# axiom_beta_interface_dummy_v0_12.net
KiCad netlist of a schematic drawn in EAGLE
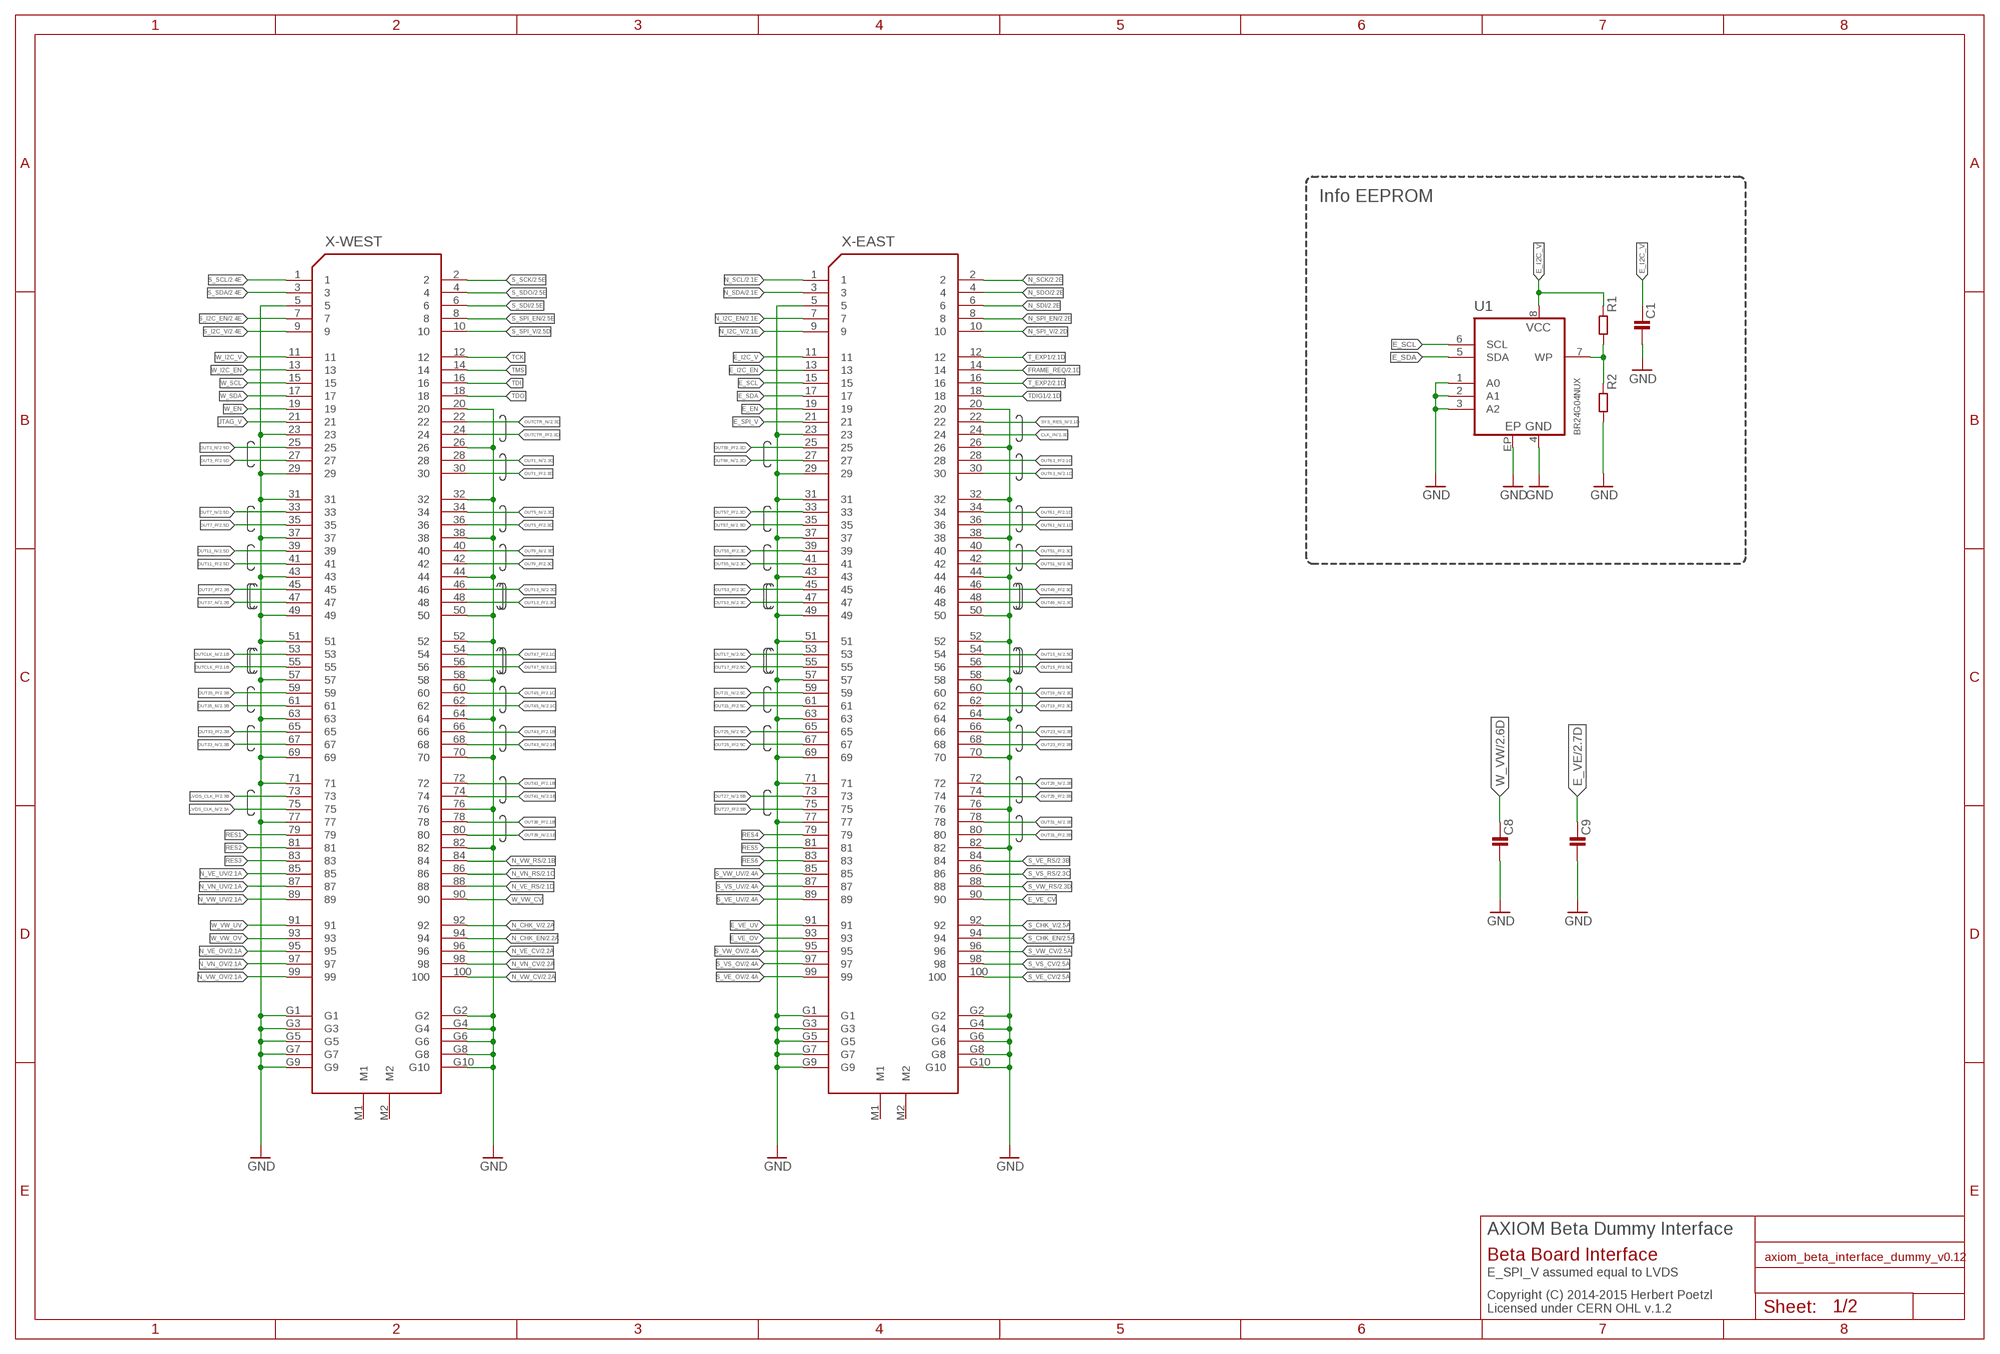
[diagram p0: schematic, sheet 1]
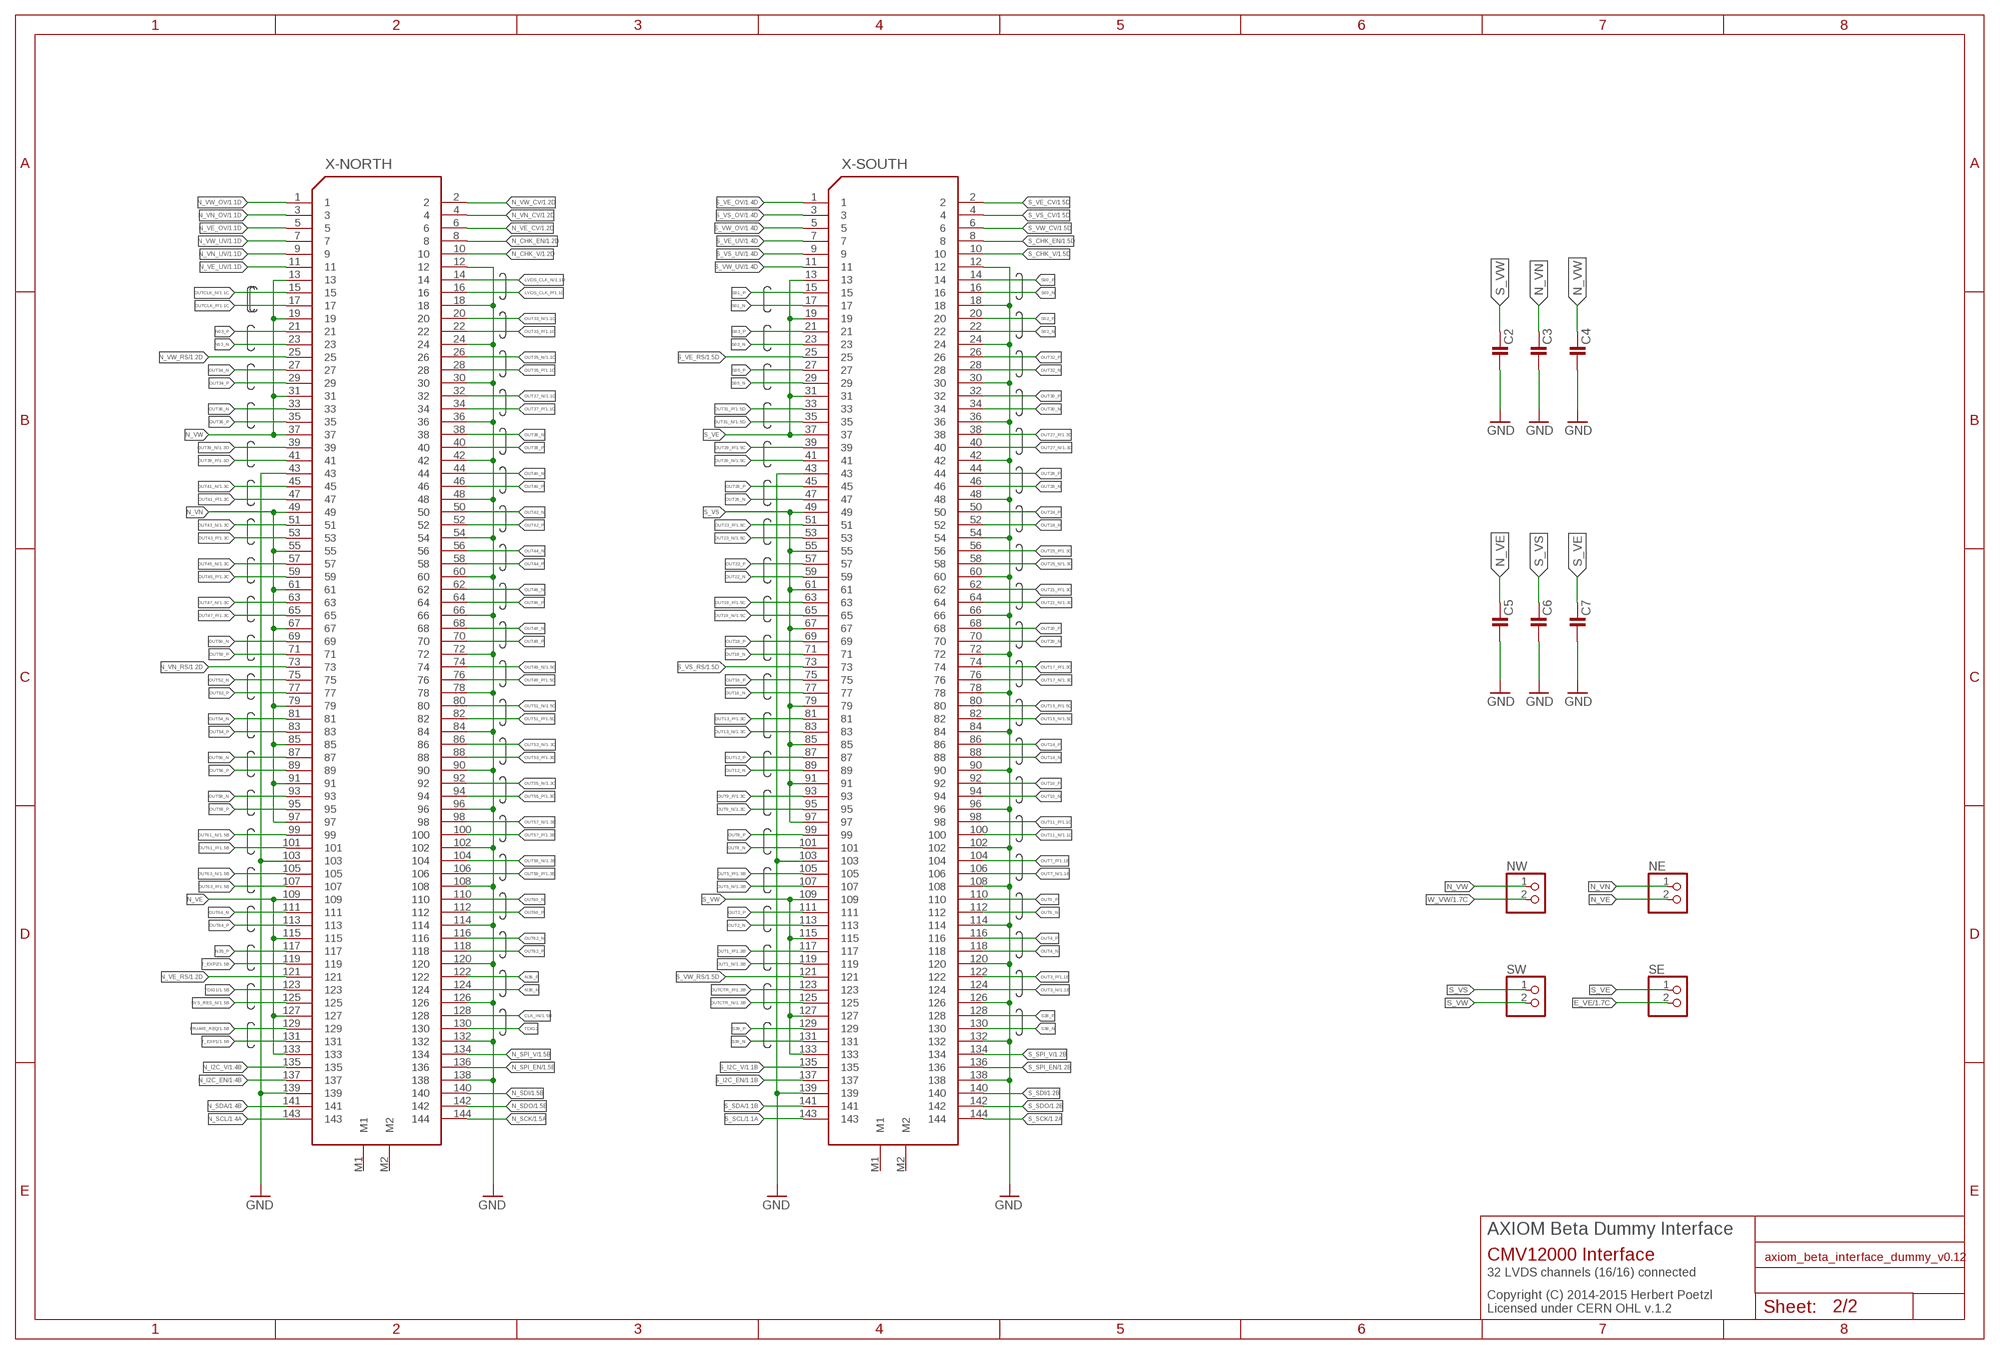
[diagram p1: schematic, sheet 2]

(export (version "E")
  (design (tool "Eeschema 10.0.6"))
  (components
    (comp (ref "C2")
      (value "C0805-B")
      (footprint "eagle-import:0805-B")
      (libsource (lib "eagle-import") (part "C0805-B"))
    )
    (comp (ref "C3")
      (value "C0805-B")
      (footprint "eagle-import:0805-B")
      (libsource (lib "eagle-import") (part "C0805-B"))
    )
    (comp (ref "C4")
      (value "C0805-B")
      (footprint "eagle-import:0805-B")
      (libsource (lib "eagle-import") (part "C0805-B"))
    )
    (comp (ref "C5")
      (value "C0805-B")
      (footprint "eagle-import:0805-B")
      (libsource (lib "eagle-import") (part "C0805-B"))
    )
    (comp (ref "C6")
      (value "C0805-B")
      (footprint "eagle-import:0805-B")
      (libsource (lib "eagle-import") (part "C0805-B"))
    )
    (comp (ref "C7")
      (value "C0805-B")
      (footprint "eagle-import:0805-B")
      (libsource (lib "eagle-import") (part "C0805-B"))
    )
    (comp (ref "NE")
      (value "PINHD-1X02_2.54")
      (footprint "eagle-import:1X02")
      (libsource (lib "eagle-import") (part "PINHD-1X02_2.54"))
    )
    (comp (ref "NW")
      (value "PINHD-1X02_2.54")
      (footprint "eagle-import:1X02")
      (libsource (lib "eagle-import") (part "PINHD-1X02_2.54"))
    )
    (comp (ref "SE")
      (value "PINHD-1X02_2.54")
      (footprint "eagle-import:1X02")
      (libsource (lib "eagle-import") (part "PINHD-1X02_2.54"))
    )
    (comp (ref "SW")
      (value "PINHD-1X02_2.54")
      (footprint "eagle-import:1X02")
      (libsource (lib "eagle-import") (part "PINHD-1X02_2.54"))
    )
    (comp (ref "X-NORTH")
      (value "FX10-144S")
      (footprint "eagle-import:FX10A-144S")
      (libsource (lib "eagle-import") (part "FX10-144S"))
    )
    (comp (ref "X-SOUTH")
      (value "FX10-144S")
      (footprint "eagle-import:FX10A-144S")
      (libsource (lib "eagle-import") (part "FX10-144S"))
    )
    (comp (ref "C1")
      (value "C0402-B")
      (footprint "eagle-import:0402-B")
      (libsource (lib "eagle-import") (part "C0402-B"))
    )
    (comp (ref "C8")
      (value "C0805-B")
      (footprint "eagle-import:0805-B")
      (libsource (lib "eagle-import") (part "C0805-B"))
    )
    (comp (ref "C9")
      (value "C0805-B")
      (footprint "eagle-import:0805-B")
      (libsource (lib "eagle-import") (part "C0805-B"))
    )
    (comp (ref "R1")
      (value "R0402-B")
      (footprint "eagle-import:0402-B")
      (libsource (lib "eagle-import") (part "R0402-B"))
    )
    (comp (ref "R2")
      (value "R0402-B")
      (footprint "eagle-import:0402-B")
      (libsource (lib "eagle-import") (part "R0402-B"))
    )
    (comp (ref "U1")
      (value "BR24G04NUX")
      (footprint "eagle-import:DFN200X300X100-9N")
      (libsource (lib "eagle-import") (part "BR24G04NUX"))
    )
    (comp (ref "X-EAST")
      (value "FX10-100/10P")
      (footprint "eagle-import:FX10A-100P_10")
      (libsource (lib "eagle-import") (part "FX10-100/10P"))
    )
    (comp (ref "X-WEST")
      (value "FX10-100/10P")
      (footprint "eagle-import:FX10A-100P_10")
      (libsource (lib "eagle-import") (part "FX10-100/10P"))
    )
  )
  (nets
    (net (code "1") (name "CLK_IN") (class "Default")
      (node (ref "X-EAST") (pin "24") (pinfunction "24_24") (pintype "bidirectional"))
      (node (ref "X-NORTH") (pin "128") (pinfunction "128_128") (pintype "bidirectional"))
    )
    (net (code "2") (name "E_EN") (class "Default")
      (node (ref "X-EAST") (pin "19") (pinfunction "19_19") (pintype "bidirectional"))
    )
    (net (code "3") (name "E_I2C_EN") (class "Default")
      (node (ref "X-EAST") (pin "13") (pinfunction "13_13") (pintype "bidirectional"))
    )
    (net (code "4") (name "E_I2C_V") (class "Default")
      (node (ref "C1") (pin "1") (pinfunction "1_1") (pintype "passive"))
      (node (ref "R1") (pin "1") (pinfunction "1_1") (pintype "passive"))
      (node (ref "U1") (pin "8") (pinfunction "VCC_8") (pintype "power_in"))
      (node (ref "X-EAST") (pin "11") (pinfunction "11_11") (pintype "bidirectional"))
    )
    (net (code "5") (name "E_SCL") (class "Default")
      (node (ref "U1") (pin "6") (pinfunction "SCL_6") (pintype "input"))
      (node (ref "X-EAST") (pin "15") (pinfunction "15_15") (pintype "bidirectional"))
    )
    (net (code "6") (name "E_SDA") (class "Default")
      (node (ref "U1") (pin "5") (pinfunction "SDA_5") (pintype "bidirectional"))
      (node (ref "X-EAST") (pin "17") (pinfunction "17_17") (pintype "bidirectional"))
    )
    (net (code "7") (name "E_SPI_V") (class "Default")
      (node (ref "X-EAST") (pin "21") (pinfunction "21_21") (pintype "bidirectional"))
    )
    (net (code "8") (name "E_VE") (class "Default")
      (node (ref "C9") (pin "1") (pinfunction "1_1") (pintype "passive"))
      (node (ref "SE") (pin "2") (pinfunction "2_2") (pintype "passive"))
    )
    (net (code "9") (name "E_VE_CV") (class "Default")
      (node (ref "X-EAST") (pin "90") (pinfunction "90_90") (pintype "bidirectional"))
    )
    (net (code "10") (name "E_VE_OV") (class "Default")
      (node (ref "X-EAST") (pin "93") (pinfunction "93_93") (pintype "bidirectional"))
    )
    (net (code "11") (name "E_VE_UV") (class "Default")
      (node (ref "X-EAST") (pin "91") (pinfunction "91_91") (pintype "bidirectional"))
    )
    (net (code "12") (name "FRAME_REQ") (class "Default")
      (node (ref "X-EAST") (pin "14") (pinfunction "14_14") (pintype "bidirectional"))
      (node (ref "X-NORTH") (pin "129") (pinfunction "129_129") (pintype "bidirectional"))
    )
    (net (code "13") (name "GND") (class "Default")
      (node (ref "C1") (pin "2") (pinfunction "2_2") (pintype "passive"))
      (node (ref "C2") (pin "2") (pinfunction "2_2") (pintype "passive"))
      (node (ref "C3") (pin "2") (pinfunction "2_2") (pintype "passive"))
      (node (ref "C4") (pin "2") (pinfunction "2_2") (pintype "passive"))
      (node (ref "C5") (pin "2") (pinfunction "2_2") (pintype "passive"))
      (node (ref "C6") (pin "2") (pinfunction "2_2") (pintype "passive"))
      (node (ref "C7") (pin "2") (pinfunction "2_2") (pintype "passive"))
      (node (ref "C8") (pin "2") (pinfunction "2_2") (pintype "passive"))
      (node (ref "C9") (pin "2") (pinfunction "2_2") (pintype "passive"))
      (node (ref "R2") (pin "2") (pinfunction "2_2") (pintype "passive"))
      (node (ref "U1") (pin "1") (pinfunction "A0_1") (pintype "input"))
      (node (ref "U1") (pin "2") (pinfunction "A1_2") (pintype "input"))
      (node (ref "U1") (pin "3") (pinfunction "A2_3") (pintype "input"))
      (node (ref "U1") (pin "4") (pinfunction "GND_4") (pintype "passive"))
      (node (ref "U1") (pin "EP") (pinfunction "EP_EP") (pintype "passive"))
      (node (ref "X-EAST") (pin "20") (pinfunction "20_20") (pintype "bidirectional"))
      (node (ref "X-EAST") (pin "23") (pinfunction "23_23") (pintype "bidirectional"))
      (node (ref "X-EAST") (pin "26") (pinfunction "26_26") (pintype "bidirectional"))
      (node (ref "X-EAST") (pin "29") (pinfunction "29_29") (pintype "bidirectional"))
      (node (ref "X-EAST") (pin "31") (pinfunction "31_31") (pintype "bidirectional"))
      (node (ref "X-EAST") (pin "32") (pinfunction "32_32") (pintype "bidirectional"))
      (node (ref "X-EAST") (pin "37") (pinfunction "37_37") (pintype "bidirectional"))
      (node (ref "X-EAST") (pin "38") (pinfunction "38_38") (pintype "bidirectional"))
      (node (ref "X-EAST") (pin "43") (pinfunction "43_43") (pintype "bidirectional"))
      (node (ref "X-EAST") (pin "44") (pinfunction "44_44") (pintype "bidirectional"))
      (node (ref "X-EAST") (pin "49") (pinfunction "49_49") (pintype "bidirectional"))
      (node (ref "X-EAST") (pin "5") (pinfunction "5_5") (pintype "bidirectional"))
      (node (ref "X-EAST") (pin "50") (pinfunction "50_50") (pintype "bidirectional"))
      (node (ref "X-EAST") (pin "51") (pinfunction "51_51") (pintype "bidirectional"))
      (node (ref "X-EAST") (pin "52") (pinfunction "52_52") (pintype "bidirectional"))
      (node (ref "X-EAST") (pin "57") (pinfunction "57_57") (pintype "bidirectional"))
      (node (ref "X-EAST") (pin "58") (pinfunction "58_58") (pintype "bidirectional"))
      (node (ref "X-EAST") (pin "63") (pinfunction "63_63") (pintype "bidirectional"))
      (node (ref "X-EAST") (pin "64") (pinfunction "64_64") (pintype "bidirectional"))
      (node (ref "X-EAST") (pin "69") (pinfunction "69_69") (pintype "bidirectional"))
      (node (ref "X-EAST") (pin "70") (pinfunction "70_70") (pintype "bidirectional"))
      (node (ref "X-EAST") (pin "71") (pinfunction "71_71") (pintype "bidirectional"))
      (node (ref "X-EAST") (pin "76") (pinfunction "76_76") (pintype "bidirectional"))
      (node (ref "X-EAST") (pin "77") (pinfunction "77_77") (pintype "bidirectional"))
      (node (ref "X-EAST") (pin "82") (pinfunction "82_82") (pintype "bidirectional"))
      (node (ref "X-EAST") (pin "G1") (pinfunction "G1_G1") (pintype "bidirectional"))
      (node (ref "X-EAST") (pin "G10") (pinfunction "G10_G10") (pintype "bidirectional"))
      (node (ref "X-EAST") (pin "G2") (pinfunction "G2_G2") (pintype "bidirectional"))
      (node (ref "X-EAST") (pin "G3") (pinfunction "G3_G3") (pintype "bidirectional"))
      (node (ref "X-EAST") (pin "G4") (pinfunction "G4_G4") (pintype "bidirectional"))
      (node (ref "X-EAST") (pin "G5") (pinfunction "G5_G5") (pintype "bidirectional"))
      (node (ref "X-EAST") (pin "G6") (pinfunction "G6_G6") (pintype "bidirectional"))
      (node (ref "X-EAST") (pin "G7") (pinfunction "G7_G7") (pintype "bidirectional"))
      (node (ref "X-EAST") (pin "G8") (pinfunction "G8_G8") (pintype "bidirectional"))
      (node (ref "X-EAST") (pin "G9") (pinfunction "G9_G9") (pintype "bidirectional"))
      (node (ref "X-NORTH") (pin "102") (pinfunction "102_102") (pintype "bidirectional"))
      (node (ref "X-NORTH") (pin "103") (pinfunction "103_103") (pintype "bidirectional"))
      (node (ref "X-NORTH") (pin "108") (pinfunction "108_108") (pintype "bidirectional"))
      (node (ref "X-NORTH") (pin "114") (pinfunction "114_114") (pintype "bidirectional"))
      (node (ref "X-NORTH") (pin "12") (pinfunction "12_12") (pintype "bidirectional"))
      (node (ref "X-NORTH") (pin "120") (pinfunction "120_120") (pintype "bidirectional"))
      (node (ref "X-NORTH") (pin "126") (pinfunction "126_126") (pintype "bidirectional"))
      (node (ref "X-NORTH") (pin "132") (pinfunction "132_132") (pintype "bidirectional"))
      (node (ref "X-NORTH") (pin "138") (pinfunction "138_138") (pintype "bidirectional"))
      (node (ref "X-NORTH") (pin "139") (pinfunction "139_139") (pintype "bidirectional"))
      (node (ref "X-NORTH") (pin "18") (pinfunction "18_18") (pintype "bidirectional"))
      (node (ref "X-NORTH") (pin "24") (pinfunction "24_24") (pintype "bidirectional"))
      (node (ref "X-NORTH") (pin "30") (pinfunction "30_30") (pintype "bidirectional"))
      (node (ref "X-NORTH") (pin "36") (pinfunction "36_36") (pintype "bidirectional"))
      (node (ref "X-NORTH") (pin "42") (pinfunction "42_42") (pintype "bidirectional"))
      (node (ref "X-NORTH") (pin "43") (pinfunction "43_43") (pintype "bidirectional"))
      (node (ref "X-NORTH") (pin "48") (pinfunction "48_48") (pintype "bidirectional"))
      (node (ref "X-NORTH") (pin "54") (pinfunction "54_54") (pintype "bidirectional"))
      (node (ref "X-NORTH") (pin "60") (pinfunction "60_60") (pintype "bidirectional"))
      (node (ref "X-NORTH") (pin "66") (pinfunction "66_66") (pintype "bidirectional"))
      (node (ref "X-NORTH") (pin "72") (pinfunction "72_72") (pintype "bidirectional"))
      (node (ref "X-NORTH") (pin "78") (pinfunction "78_78") (pintype "bidirectional"))
      (node (ref "X-NORTH") (pin "84") (pinfunction "84_84") (pintype "bidirectional"))
      (node (ref "X-NORTH") (pin "90") (pinfunction "90_90") (pintype "bidirectional"))
      (node (ref "X-NORTH") (pin "96") (pinfunction "96_96") (pintype "bidirectional"))
      (node (ref "X-SOUTH") (pin "102") (pinfunction "102_102") (pintype "bidirectional"))
      (node (ref "X-SOUTH") (pin "103") (pinfunction "103_103") (pintype "bidirectional"))
      (node (ref "X-SOUTH") (pin "108") (pinfunction "108_108") (pintype "bidirectional"))
      (node (ref "X-SOUTH") (pin "114") (pinfunction "114_114") (pintype "bidirectional"))
      (node (ref "X-SOUTH") (pin "12") (pinfunction "12_12") (pintype "bidirectional"))
      (node (ref "X-SOUTH") (pin "120") (pinfunction "120_120") (pintype "bidirectional"))
      (node (ref "X-SOUTH") (pin "126") (pinfunction "126_126") (pintype "bidirectional"))
      (node (ref "X-SOUTH") (pin "132") (pinfunction "132_132") (pintype "bidirectional"))
      (node (ref "X-SOUTH") (pin "138") (pinfunction "138_138") (pintype "bidirectional"))
      (node (ref "X-SOUTH") (pin "139") (pinfunction "139_139") (pintype "bidirectional"))
      (node (ref "X-SOUTH") (pin "18") (pinfunction "18_18") (pintype "bidirectional"))
      (node (ref "X-SOUTH") (pin "24") (pinfunction "24_24") (pintype "bidirectional"))
      (node (ref "X-SOUTH") (pin "30") (pinfunction "30_30") (pintype "bidirectional"))
      (node (ref "X-SOUTH") (pin "36") (pinfunction "36_36") (pintype "bidirectional"))
      (node (ref "X-SOUTH") (pin "42") (pinfunction "42_42") (pintype "bidirectional"))
      (node (ref "X-SOUTH") (pin "43") (pinfunction "43_43") (pintype "bidirectional"))
      (node (ref "X-SOUTH") (pin "48") (pinfunction "48_48") (pintype "bidirectional"))
      (node (ref "X-SOUTH") (pin "54") (pinfunction "54_54") (pintype "bidirectional"))
      (node (ref "X-SOUTH") (pin "60") (pinfunction "60_60") (pintype "bidirectional"))
      (node (ref "X-SOUTH") (pin "66") (pinfunction "66_66") (pintype "bidirectional"))
      (node (ref "X-SOUTH") (pin "72") (pinfunction "72_72") (pintype "bidirectional"))
      (node (ref "X-SOUTH") (pin "78") (pinfunction "78_78") (pintype "bidirectional"))
      (node (ref "X-SOUTH") (pin "84") (pinfunction "84_84") (pintype "bidirectional"))
      (node (ref "X-SOUTH") (pin "90") (pinfunction "90_90") (pintype "bidirectional"))
      (node (ref "X-SOUTH") (pin "96") (pinfunction "96_96") (pintype "bidirectional"))
      (node (ref "X-WEST") (pin "20") (pinfunction "20_20") (pintype "bidirectional"))
      (node (ref "X-WEST") (pin "23") (pinfunction "23_23") (pintype "bidirectional"))
      (node (ref "X-WEST") (pin "26") (pinfunction "26_26") (pintype "bidirectional"))
      (node (ref "X-WEST") (pin "29") (pinfunction "29_29") (pintype "bidirectional"))
      (node (ref "X-WEST") (pin "31") (pinfunction "31_31") (pintype "bidirectional"))
      (node (ref "X-WEST") (pin "32") (pinfunction "32_32") (pintype "bidirectional"))
      (node (ref "X-WEST") (pin "37") (pinfunction "37_37") (pintype "bidirectional"))
      (node (ref "X-WEST") (pin "38") (pinfunction "38_38") (pintype "bidirectional"))
      (node (ref "X-WEST") (pin "43") (pinfunction "43_43") (pintype "bidirectional"))
      (node (ref "X-WEST") (pin "44") (pinfunction "44_44") (pintype "bidirectional"))
      (node (ref "X-WEST") (pin "49") (pinfunction "49_49") (pintype "bidirectional"))
      (node (ref "X-WEST") (pin "5") (pinfunction "5_5") (pintype "bidirectional"))
      (node (ref "X-WEST") (pin "50") (pinfunction "50_50") (pintype "bidirectional"))
      (node (ref "X-WEST") (pin "51") (pinfunction "51_51") (pintype "bidirectional"))
      (node (ref "X-WEST") (pin "52") (pinfunction "52_52") (pintype "bidirectional"))
      (node (ref "X-WEST") (pin "57") (pinfunction "57_57") (pintype "bidirectional"))
      (node (ref "X-WEST") (pin "58") (pinfunction "58_58") (pintype "bidirectional"))
      (node (ref "X-WEST") (pin "63") (pinfunction "63_63") (pintype "bidirectional"))
      (node (ref "X-WEST") (pin "64") (pinfunction "64_64") (pintype "bidirectional"))
      (node (ref "X-WEST") (pin "69") (pinfunction "69_69") (pintype "bidirectional"))
      (node (ref "X-WEST") (pin "70") (pinfunction "70_70") (pintype "bidirectional"))
      (node (ref "X-WEST") (pin "71") (pinfunction "71_71") (pintype "bidirectional"))
      (node (ref "X-WEST") (pin "76") (pinfunction "76_76") (pintype "bidirectional"))
      (node (ref "X-WEST") (pin "77") (pinfunction "77_77") (pintype "bidirectional"))
      (node (ref "X-WEST") (pin "82") (pinfunction "82_82") (pintype "bidirectional"))
      (node (ref "X-WEST") (pin "G1") (pinfunction "G1_G1") (pintype "bidirectional"))
      (node (ref "X-WEST") (pin "G10") (pinfunction "G10_G10") (pintype "bidirectional"))
      (node (ref "X-WEST") (pin "G2") (pinfunction "G2_G2") (pintype "bidirectional"))
      (node (ref "X-WEST") (pin "G3") (pinfunction "G3_G3") (pintype "bidirectional"))
      (node (ref "X-WEST") (pin "G4") (pinfunction "G4_G4") (pintype "bidirectional"))
      (node (ref "X-WEST") (pin "G5") (pinfunction "G5_G5") (pintype "bidirectional"))
      (node (ref "X-WEST") (pin "G6") (pinfunction "G6_G6") (pintype "bidirectional"))
      (node (ref "X-WEST") (pin "G7") (pinfunction "G7_G7") (pintype "bidirectional"))
      (node (ref "X-WEST") (pin "G8") (pinfunction "G8_G8") (pintype "bidirectional"))
      (node (ref "X-WEST") (pin "G9") (pinfunction "G9_G9") (pintype "bidirectional"))
    )
    (net (code "14") (name "JTAG_V") (class "Default")
      (node (ref "X-WEST") (pin "21") (pinfunction "21_21") (pintype "bidirectional"))
    )
    (net (code "15") (name "LVDS_CLK_N") (class "Default")
      (node (ref "X-NORTH") (pin "14") (pinfunction "14_14") (pintype "bidirectional"))
      (node (ref "X-WEST") (pin "75") (pinfunction "75_75") (pintype "bidirectional"))
    )
    (net (code "16") (name "LVDS_CLK_P") (class "Default")
      (node (ref "X-NORTH") (pin "16") (pinfunction "16_16") (pintype "bidirectional"))
      (node (ref "X-WEST") (pin "73") (pinfunction "73_73") (pintype "bidirectional"))
    )
    (net (code "17") (name "N03_N") (class "Default")
      (node (ref "X-NORTH") (pin "23") (pinfunction "23_23") (pintype "bidirectional"))
    )
    (net (code "18") (name "N03_P") (class "Default")
      (node (ref "X-NORTH") (pin "21") (pinfunction "21_21") (pintype "bidirectional"))
    )
    (net (code "19") (name "N35_P") (class "Default")
      (node (ref "X-NORTH") (pin "117") (pinfunction "117_117") (pintype "bidirectional"))
    )
    (net (code "20") (name "N36_N") (class "Default")
      (node (ref "X-NORTH") (pin "124") (pinfunction "124_124") (pintype "bidirectional"))
    )
    (net (code "21") (name "N36_P") (class "Default")
      (node (ref "X-NORTH") (pin "122") (pinfunction "122_122") (pintype "bidirectional"))
    )
    (net (code "22") (name "N_CHK_EN") (class "Default")
      (node (ref "X-NORTH") (pin "8") (pinfunction "8_8") (pintype "bidirectional"))
      (node (ref "X-WEST") (pin "94") (pinfunction "94_94") (pintype "bidirectional"))
    )
    (net (code "23") (name "N_CHK_V") (class "Default")
      (node (ref "X-NORTH") (pin "10") (pinfunction "10_10") (pintype "bidirectional"))
      (node (ref "X-WEST") (pin "92") (pinfunction "92_92") (pintype "bidirectional"))
    )
    (net (code "24") (name "N_I2C_EN") (class "Default")
      (node (ref "X-EAST") (pin "7") (pinfunction "7_7") (pintype "bidirectional"))
      (node (ref "X-NORTH") (pin "137") (pinfunction "137_137") (pintype "bidirectional"))
    )
    (net (code "25") (name "N_I2C_V") (class "Default")
      (node (ref "X-EAST") (pin "9") (pinfunction "9_9") (pintype "bidirectional"))
      (node (ref "X-NORTH") (pin "135") (pinfunction "135_135") (pintype "bidirectional"))
    )
    (net (code "26") (name "N_SCK") (class "Default")
      (node (ref "X-EAST") (pin "2") (pinfunction "2_2") (pintype "bidirectional"))
      (node (ref "X-NORTH") (pin "144") (pinfunction "144_144") (pintype "bidirectional"))
    )
    (net (code "27") (name "N_SCL") (class "Default")
      (node (ref "X-EAST") (pin "1") (pinfunction "1_1") (pintype "bidirectional"))
      (node (ref "X-NORTH") (pin "143") (pinfunction "143_143") (pintype "bidirectional"))
    )
    (net (code "28") (name "N_SDA") (class "Default")
      (node (ref "X-EAST") (pin "3") (pinfunction "3_3") (pintype "bidirectional"))
      (node (ref "X-NORTH") (pin "141") (pinfunction "141_141") (pintype "bidirectional"))
    )
    (net (code "29") (name "N_SDI") (class "Default")
      (node (ref "X-EAST") (pin "6") (pinfunction "6_6") (pintype "bidirectional"))
      (node (ref "X-NORTH") (pin "140") (pinfunction "140_140") (pintype "bidirectional"))
    )
    (net (code "30") (name "N_SDO") (class "Default")
      (node (ref "X-EAST") (pin "4") (pinfunction "4_4") (pintype "bidirectional"))
      (node (ref "X-NORTH") (pin "142") (pinfunction "142_142") (pintype "bidirectional"))
    )
    (net (code "31") (name "N_SPI_EN") (class "Default")
      (node (ref "X-EAST") (pin "8") (pinfunction "8_8") (pintype "bidirectional"))
      (node (ref "X-NORTH") (pin "136") (pinfunction "136_136") (pintype "bidirectional"))
    )
    (net (code "32") (name "N_SPI_V") (class "Default")
      (node (ref "X-EAST") (pin "10") (pinfunction "10_10") (pintype "bidirectional"))
      (node (ref "X-NORTH") (pin "134") (pinfunction "134_134") (pintype "bidirectional"))
    )
    (net (code "33") (name "N_VE") (class "Default")
      (node (ref "C5") (pin "1") (pinfunction "1_1") (pintype "passive"))
      (node (ref "NE") (pin "2") (pinfunction "2_2") (pintype "passive"))
      (node (ref "X-NORTH") (pin "109") (pinfunction "109_109") (pintype "bidirectional"))
      (node (ref "X-NORTH") (pin "115") (pinfunction "115_115") (pintype "bidirectional"))
      (node (ref "X-NORTH") (pin "127") (pinfunction "127_127") (pintype "bidirectional"))
      (node (ref "X-NORTH") (pin "133") (pinfunction "133_133") (pintype "bidirectional"))
    )
    (net (code "34") (name "N_VE_CV") (class "Default")
      (node (ref "X-NORTH") (pin "6") (pinfunction "6_6") (pintype "bidirectional"))
      (node (ref "X-WEST") (pin "96") (pinfunction "96_96") (pintype "bidirectional"))
    )
    (net (code "35") (name "N_VE_OV") (class "Default")
      (node (ref "X-NORTH") (pin "5") (pinfunction "5_5") (pintype "bidirectional"))
      (node (ref "X-WEST") (pin "95") (pinfunction "95_95") (pintype "bidirectional"))
    )
    (net (code "36") (name "N_VE_RS") (class "Default")
      (node (ref "X-NORTH") (pin "121") (pinfunction "121_121") (pintype "bidirectional"))
      (node (ref "X-WEST") (pin "88") (pinfunction "88_88") (pintype "bidirectional"))
    )
    (net (code "37") (name "N_VE_UV") (class "Default")
      (node (ref "X-NORTH") (pin "11") (pinfunction "11_11") (pintype "bidirectional"))
      (node (ref "X-WEST") (pin "85") (pinfunction "85_85") (pintype "bidirectional"))
    )
    (net (code "38") (name "N_VN") (class "Default")
      (node (ref "C3") (pin "1") (pinfunction "1_1") (pintype "passive"))
      (node (ref "NE") (pin "1") (pinfunction "1_1") (pintype "passive"))
      (node (ref "X-NORTH") (pin "49") (pinfunction "49_49") (pintype "bidirectional"))
      (node (ref "X-NORTH") (pin "55") (pinfunction "55_55") (pintype "bidirectional"))
      (node (ref "X-NORTH") (pin "61") (pinfunction "61_61") (pintype "bidirectional"))
      (node (ref "X-NORTH") (pin "67") (pinfunction "67_67") (pintype "bidirectional"))
      (node (ref "X-NORTH") (pin "79") (pinfunction "79_79") (pintype "bidirectional"))
      (node (ref "X-NORTH") (pin "85") (pinfunction "85_85") (pintype "bidirectional"))
      (node (ref "X-NORTH") (pin "91") (pinfunction "91_91") (pintype "bidirectional"))
      (node (ref "X-NORTH") (pin "97") (pinfunction "97_97") (pintype "bidirectional"))
    )
    (net (code "39") (name "N_VN_CV") (class "Default")
      (node (ref "X-NORTH") (pin "4") (pinfunction "4_4") (pintype "bidirectional"))
      (node (ref "X-WEST") (pin "98") (pinfunction "98_98") (pintype "bidirectional"))
    )
    (net (code "40") (name "N_VN_OV") (class "Default")
      (node (ref "X-NORTH") (pin "3") (pinfunction "3_3") (pintype "bidirectional"))
      (node (ref "X-WEST") (pin "97") (pinfunction "97_97") (pintype "bidirectional"))
    )
    (net (code "41") (name "N_VN_RS") (class "Default")
      (node (ref "X-NORTH") (pin "73") (pinfunction "73_73") (pintype "bidirectional"))
      (node (ref "X-WEST") (pin "86") (pinfunction "86_86") (pintype "bidirectional"))
    )
    (net (code "42") (name "N_VN_UV") (class "Default")
      (node (ref "X-NORTH") (pin "9") (pinfunction "9_9") (pintype "bidirectional"))
      (node (ref "X-WEST") (pin "87") (pinfunction "87_87") (pintype "bidirectional"))
    )
    (net (code "43") (name "N_VW") (class "Default")
      (node (ref "C4") (pin "1") (pinfunction "1_1") (pintype "passive"))
      (node (ref "NW") (pin "1") (pinfunction "1_1") (pintype "passive"))
      (node (ref "X-NORTH") (pin "13") (pinfunction "13_13") (pintype "bidirectional"))
      (node (ref "X-NORTH") (pin "19") (pinfunction "19_19") (pintype "bidirectional"))
      (node (ref "X-NORTH") (pin "31") (pinfunction "31_31") (pintype "bidirectional"))
      (node (ref "X-NORTH") (pin "37") (pinfunction "37_37") (pintype "bidirectional"))
    )
    (net (code "44") (name "N_VW_CV") (class "Default")
      (node (ref "X-NORTH") (pin "2") (pinfunction "2_2") (pintype "bidirectional"))
      (node (ref "X-WEST") (pin "100") (pinfunction "100_100") (pintype "bidirectional"))
    )
    (net (code "45") (name "N_VW_OV") (class "Default")
      (node (ref "X-NORTH") (pin "1") (pinfunction "1_1") (pintype "bidirectional"))
      (node (ref "X-WEST") (pin "99") (pinfunction "99_99") (pintype "bidirectional"))
    )
    (net (code "46") (name "N_VW_RS") (class "Default")
      (node (ref "X-NORTH") (pin "25") (pinfunction "25_25") (pintype "bidirectional"))
      (node (ref "X-WEST") (pin "84") (pinfunction "84_84") (pintype "bidirectional"))
    )
    (net (code "47") (name "N_VW_UV") (class "Default")
      (node (ref "X-NORTH") (pin "7") (pinfunction "7_7") (pintype "bidirectional"))
      (node (ref "X-WEST") (pin "89") (pinfunction "89_89") (pintype "bidirectional"))
    )
    (net (code "48") (name "Net-(U1-WP)") (class "Default")
      (node (ref "R1") (pin "2") (pinfunction "2_2") (pintype "passive"))
      (node (ref "R2") (pin "1") (pinfunction "1_1") (pintype "passive"))
      (node (ref "U1") (pin "7") (pinfunction "WP_7") (pintype "input"))
    )
    (net (code "49") (name "OUT1_N") (class "Default")
      (node (ref "X-SOUTH") (pin "119") (pinfunction "119_119") (pintype "bidirectional"))
      (node (ref "X-WEST") (pin "28") (pinfunction "28_28") (pintype "bidirectional"))
    )
    (net (code "50") (name "OUT1_P") (class "Default")
      (node (ref "X-SOUTH") (pin "117") (pinfunction "117_117") (pintype "bidirectional"))
      (node (ref "X-WEST") (pin "30") (pinfunction "30_30") (pintype "bidirectional"))
    )
    (net (code "51") (name "OUT2_N") (class "Default")
      (node (ref "X-SOUTH") (pin "113") (pinfunction "113_113") (pintype "bidirectional"))
    )
    (net (code "52") (name "OUT2_P") (class "Default")
      (node (ref "X-SOUTH") (pin "111") (pinfunction "111_111") (pintype "bidirectional"))
    )
    (net (code "53") (name "OUT3_N") (class "Default")
      (node (ref "X-SOUTH") (pin "124") (pinfunction "124_124") (pintype "bidirectional"))
      (node (ref "X-WEST") (pin "25") (pinfunction "25_25") (pintype "bidirectional"))
    )
    (net (code "54") (name "OUT3_P") (class "Default")
      (node (ref "X-SOUTH") (pin "122") (pinfunction "122_122") (pintype "bidirectional"))
      (node (ref "X-WEST") (pin "27") (pinfunction "27_27") (pintype "bidirectional"))
    )
    (net (code "55") (name "OUT4_N") (class "Default")
      (node (ref "X-SOUTH") (pin "118") (pinfunction "118_118") (pintype "bidirectional"))
    )
    (net (code "56") (name "OUT4_P") (class "Default")
      (node (ref "X-SOUTH") (pin "116") (pinfunction "116_116") (pintype "bidirectional"))
    )
    (net (code "57") (name "OUT5_N") (class "Default")
      (node (ref "X-SOUTH") (pin "107") (pinfunction "107_107") (pintype "bidirectional"))
      (node (ref "X-WEST") (pin "34") (pinfunction "34_34") (pintype "bidirectional"))
    )
    (net (code "58") (name "OUT5_P") (class "Default")
      (node (ref "X-SOUTH") (pin "105") (pinfunction "105_105") (pintype "bidirectional"))
      (node (ref "X-WEST") (pin "36") (pinfunction "36_36") (pintype "bidirectional"))
    )
    (net (code "59") (name "OUT6_N") (class "Default")
      (node (ref "X-SOUTH") (pin "112") (pinfunction "112_112") (pintype "bidirectional"))
    )
    (net (code "60") (name "OUT6_P") (class "Default")
      (node (ref "X-SOUTH") (pin "110") (pinfunction "110_110") (pintype "bidirectional"))
    )
    (net (code "61") (name "OUT7_N") (class "Default")
      (node (ref "X-SOUTH") (pin "106") (pinfunction "106_106") (pintype "bidirectional"))
      (node (ref "X-WEST") (pin "33") (pinfunction "33_33") (pintype "bidirectional"))
    )
    (net (code "62") (name "OUT7_P") (class "Default")
      (node (ref "X-SOUTH") (pin "104") (pinfunction "104_104") (pintype "bidirectional"))
      (node (ref "X-WEST") (pin "35") (pinfunction "35_35") (pintype "bidirectional"))
    )
    (net (code "63") (name "OUT8_N") (class "Default")
      (node (ref "X-SOUTH") (pin "101") (pinfunction "101_101") (pintype "bidirectional"))
    )
    (net (code "64") (name "OUT8_P") (class "Default")
      (node (ref "X-SOUTH") (pin "99") (pinfunction "99_99") (pintype "bidirectional"))
    )
    (net (code "65") (name "OUT9_N") (class "Default")
      (node (ref "X-SOUTH") (pin "95") (pinfunction "95_95") (pintype "bidirectional"))
      (node (ref "X-WEST") (pin "40") (pinfunction "40_40") (pintype "bidirectional"))
    )
    (net (code "66") (name "OUT9_P") (class "Default")
      (node (ref "X-SOUTH") (pin "93") (pinfunction "93_93") (pintype "bidirectional"))
      (node (ref "X-WEST") (pin "42") (pinfunction "42_42") (pintype "bidirectional"))
    )
    (net (code "67") (name "OUT10_N") (class "Default")
      (node (ref "X-SOUTH") (pin "94") (pinfunction "94_94") (pintype "bidirectional"))
    )
    (net (code "68") (name "OUT10_P") (class "Default")
      (node (ref "X-SOUTH") (pin "92") (pinfunction "92_92") (pintype "bidirectional"))
    )
    (net (code "69") (name "OUT11_N") (class "Default")
      (node (ref "X-SOUTH") (pin "100") (pinfunction "100_100") (pintype "bidirectional"))
      (node (ref "X-WEST") (pin "39") (pinfunction "39_39") (pintype "bidirectional"))
    )
    (net (code "70") (name "OUT11_P") (class "Default")
      (node (ref "X-SOUTH") (pin "98") (pinfunction "98_98") (pintype "bidirectional"))
      (node (ref "X-WEST") (pin "41") (pinfunction "41_41") (pintype "bidirectional"))
    )
    (net (code "71") (name "OUT12_N") (class "Default")
      (node (ref "X-SOUTH") (pin "89") (pinfunction "89_89") (pintype "bidirectional"))
    )
    (net (code "72") (name "OUT12_P") (class "Default")
      (node (ref "X-SOUTH") (pin "87") (pinfunction "87_87") (pintype "bidirectional"))
    )
    (net (code "73") (name "OUT13_N") (class "Default")
      (node (ref "X-SOUTH") (pin "83") (pinfunction "83_83") (pintype "bidirectional"))
      (node (ref "X-WEST") (pin "46") (pinfunction "46_46") (pintype "bidirectional"))
    )
    (net (code "74") (name "OUT13_P") (class "Default")
      (node (ref "X-SOUTH") (pin "81") (pinfunction "81_81") (pintype "bidirectional"))
      (node (ref "X-WEST") (pin "48") (pinfunction "48_48") (pintype "bidirectional"))
    )
    (net (code "75") (name "OUT14_N") (class "Default")
      (node (ref "X-SOUTH") (pin "88") (pinfunction "88_88") (pintype "bidirectional"))
    )
    (net (code "76") (name "OUT14_P") (class "Default")
      (node (ref "X-SOUTH") (pin "86") (pinfunction "86_86") (pintype "bidirectional"))
    )
    (net (code "77") (name "OUT15_N") (class "Default")
      (node (ref "X-EAST") (pin "54") (pinfunction "54_54") (pintype "bidirectional"))
      (node (ref "X-SOUTH") (pin "82") (pinfunction "82_82") (pintype "bidirectional"))
    )
    (net (code "78") (name "OUT15_P") (class "Default")
      (node (ref "X-EAST") (pin "56") (pinfunction "56_56") (pintype "bidirectional"))
      (node (ref "X-SOUTH") (pin "80") (pinfunction "80_80") (pintype "bidirectional"))
    )
    (net (code "79") (name "OUT16_N") (class "Default")
      (node (ref "X-SOUTH") (pin "77") (pinfunction "77_77") (pintype "bidirectional"))
    )
    (net (code "80") (name "OUT16_P") (class "Default")
      (node (ref "X-SOUTH") (pin "75") (pinfunction "75_75") (pintype "bidirectional"))
    )
    (net (code "81") (name "OUT17_N") (class "Default")
      (node (ref "X-EAST") (pin "53") (pinfunction "53_53") (pintype "bidirectional"))
      (node (ref "X-SOUTH") (pin "76") (pinfunction "76_76") (pintype "bidirectional"))
    )
    (net (code "82") (name "OUT17_P") (class "Default")
      (node (ref "X-EAST") (pin "55") (pinfunction "55_55") (pintype "bidirectional"))
      (node (ref "X-SOUTH") (pin "74") (pinfunction "74_74") (pintype "bidirectional"))
    )
    (net (code "83") (name "OUT18_N") (class "Default")
      (node (ref "X-SOUTH") (pin "71") (pinfunction "71_71") (pintype "bidirectional"))
    )
    (net (code "84") (name "OUT18_P") (class "Default")
      (node (ref "X-SOUTH") (pin "69") (pinfunction "69_69") (pintype "bidirectional"))
    )
    (net (code "85") (name "OUT19_N") (class "Default")
      (node (ref "X-EAST") (pin "60") (pinfunction "60_60") (pintype "bidirectional"))
      (node (ref "X-SOUTH") (pin "65") (pinfunction "65_65") (pintype "bidirectional"))
    )
    (net (code "86") (name "OUT19_P") (class "Default")
      (node (ref "X-EAST") (pin "62") (pinfunction "62_62") (pintype "bidirectional"))
      (node (ref "X-SOUTH") (pin "63") (pinfunction "63_63") (pintype "bidirectional"))
    )
    (net (code "87") (name "OUT20_N") (class "Default")
      (node (ref "X-SOUTH") (pin "70") (pinfunction "70_70") (pintype "bidirectional"))
    )
    (net (code "88") (name "OUT20_P") (class "Default")
      (node (ref "X-SOUTH") (pin "68") (pinfunction "68_68") (pintype "bidirectional"))
    )
    (net (code "89") (name "OUT21_N") (class "Default")
      (node (ref "X-EAST") (pin "59") (pinfunction "59_59") (pintype "bidirectional"))
      (node (ref "X-SOUTH") (pin "64") (pinfunction "64_64") (pintype "bidirectional"))
    )
    (net (code "90") (name "OUT21_P") (class "Default")
      (node (ref "X-EAST") (pin "61") (pinfunction "61_61") (pintype "bidirectional"))
      (node (ref "X-SOUTH") (pin "62") (pinfunction "62_62") (pintype "bidirectional"))
    )
    (net (code "91") (name "OUT22_N") (class "Default")
      (node (ref "X-SOUTH") (pin "59") (pinfunction "59_59") (pintype "bidirectional"))
    )
    (net (code "92") (name "OUT22_P") (class "Default")
      (node (ref "X-SOUTH") (pin "57") (pinfunction "57_57") (pintype "bidirectional"))
    )
    (net (code "93") (name "OUT23_N") (class "Default")
      (node (ref "X-EAST") (pin "66") (pinfunction "66_66") (pintype "bidirectional"))
      (node (ref "X-SOUTH") (pin "53") (pinfunction "53_53") (pintype "bidirectional"))
    )
    (net (code "94") (name "OUT23_P") (class "Default")
      (node (ref "X-EAST") (pin "68") (pinfunction "68_68") (pintype "bidirectional"))
      (node (ref "X-SOUTH") (pin "51") (pinfunction "51_51") (pintype "bidirectional"))
    )
    (net (code "95") (name "OUT24_N") (class "Default")
      (node (ref "X-SOUTH") (pin "52") (pinfunction "52_52") (pintype "bidirectional"))
    )
    (net (code "96") (name "OUT24_P") (class "Default")
      (node (ref "X-SOUTH") (pin "50") (pinfunction "50_50") (pintype "bidirectional"))
    )
    (net (code "97") (name "OUT25_N") (class "Default")
      (node (ref "X-EAST") (pin "65") (pinfunction "65_65") (pintype "bidirectional"))
      (node (ref "X-SOUTH") (pin "58") (pinfunction "58_58") (pintype "bidirectional"))
    )
    (net (code "98") (name "OUT25_P") (class "Default")
      (node (ref "X-EAST") (pin "67") (pinfunction "67_67") (pintype "bidirectional"))
      (node (ref "X-SOUTH") (pin "56") (pinfunction "56_56") (pintype "bidirectional"))
    )
    (net (code "99") (name "OUT26_N") (class "Default")
      (node (ref "X-SOUTH") (pin "47") (pinfunction "47_47") (pintype "bidirectional"))
    )
    (net (code "100") (name "OUT26_P") (class "Default")
      (node (ref "X-SOUTH") (pin "45") (pinfunction "45_45") (pintype "bidirectional"))
    )
    (net (code "101") (name "OUT27_N") (class "Default")
      (node (ref "X-EAST") (pin "73") (pinfunction "73_73") (pintype "bidirectional"))
      (node (ref "X-SOUTH") (pin "40") (pinfunction "40_40") (pintype "bidirectional"))
    )
    (net (code "102") (name "OUT27_P") (class "Default")
      (node (ref "X-EAST") (pin "75") (pinfunction "75_75") (pintype "bidirectional"))
      (node (ref "X-SOUTH") (pin "38") (pinfunction "38_38") (pintype "bidirectional"))
    )
    (net (code "103") (name "OUT28_N") (class "Default")
      (node (ref "X-SOUTH") (pin "46") (pinfunction "46_46") (pintype "bidirectional"))
    )
    (net (code "104") (name "OUT28_P") (class "Default")
      (node (ref "X-SOUTH") (pin "44") (pinfunction "44_44") (pintype "bidirectional"))
    )
    (net (code "105") (name "OUT29_N") (class "Default")
      (node (ref "X-EAST") (pin "72") (pinfunction "72_72") (pintype "bidirectional"))
      (node (ref "X-SOUTH") (pin "41") (pinfunction "41_41") (pintype "bidirectional"))
    )
    (net (code "106") (name "OUT29_P") (class "Default")
      (node (ref "X-EAST") (pin "74") (pinfunction "74_74") (pintype "bidirectional"))
      (node (ref "X-SOUTH") (pin "39") (pinfunction "39_39") (pintype "bidirectional"))
    )
    (net (code "107") (name "OUT30_N") (class "Default")
      (node (ref "X-SOUTH") (pin "34") (pinfunction "34_34") (pintype "bidirectional"))
    )
    (net (code "108") (name "OUT30_P") (class "Default")
      (node (ref "X-SOUTH") (pin "32") (pinfunction "32_32") (pintype "bidirectional"))
    )
    (net (code "109") (name "OUT31_N") (class "Default")
      (node (ref "X-EAST") (pin "78") (pinfunction "78_78") (pintype "bidirectional"))
      (node (ref "X-SOUTH") (pin "35") (pinfunction "35_35") (pintype "bidirectional"))
    )
    (net (code "110") (name "OUT31_P") (class "Default")
      (node (ref "X-EAST") (pin "80") (pinfunction "80_80") (pintype "bidirectional"))
      (node (ref "X-SOUTH") (pin "33") (pinfunction "33_33") (pintype "bidirectional"))
    )
    (net (code "111") (name "OUT32_N") (class "Default")
      (node (ref "X-SOUTH") (pin "28") (pinfunction "28_28") (pintype "bidirectional"))
    )
    (net (code "112") (name "OUT32_P") (class "Default")
      (node (ref "X-SOUTH") (pin "26") (pinfunction "26_26") (pintype "bidirectional"))
    )
    (net (code "113") (name "OUT33_N") (class "Default")
      (node (ref "X-NORTH") (pin "20") (pinfunction "20_20") (pintype "bidirectional"))
      (node (ref "X-WEST") (pin "67") (pinfunction "67_67") (pintype "bidirectional"))
    )
    (net (code "114") (name "OUT33_P") (class "Default")
      (node (ref "X-NORTH") (pin "22") (pinfunction "22_22") (pintype "bidirectional"))
      (node (ref "X-WEST") (pin "65") (pinfunction "65_65") (pintype "bidirectional"))
    )
    (net (code "115") (name "OUT34_N") (class "Default")
      (node (ref "X-NORTH") (pin "27") (pinfunction "27_27") (pintype "bidirectional"))
    )
    (net (code "116") (name "OUT34_P") (class "Default")
      (node (ref "X-NORTH") (pin "29") (pinfunction "29_29") (pintype "bidirectional"))
    )
    (net (code "117") (name "OUT35_N") (class "Default")
      (node (ref "X-NORTH") (pin "26") (pinfunction "26_26") (pintype "bidirectional"))
      (node (ref "X-WEST") (pin "61") (pinfunction "61_61") (pintype "bidirectional"))
    )
    (net (code "118") (name "OUT35_P") (class "Default")
      (node (ref "X-NORTH") (pin "28") (pinfunction "28_28") (pintype "bidirectional"))
      (node (ref "X-WEST") (pin "59") (pinfunction "59_59") (pintype "bidirectional"))
    )
    (net (code "119") (name "OUT36_N") (class "Default")
      (node (ref "X-NORTH") (pin "33") (pinfunction "33_33") (pintype "bidirectional"))
    )
    (net (code "120") (name "OUT36_P") (class "Default")
      (node (ref "X-NORTH") (pin "35") (pinfunction "35_35") (pintype "bidirectional"))
    )
    (net (code "121") (name "OUT37_N") (class "Default")
      (node (ref "X-NORTH") (pin "32") (pinfunction "32_32") (pintype "bidirectional"))
      (node (ref "X-WEST") (pin "47") (pinfunction "47_47") (pintype "bidirectional"))
    )
    (net (code "122") (name "OUT37_P") (class "Default")
      (node (ref "X-NORTH") (pin "34") (pinfunction "34_34") (pintype "bidirectional"))
      (node (ref "X-WEST") (pin "45") (pinfunction "45_45") (pintype "bidirectional"))
    )
    (net (code "123") (name "OUT38_N") (class "Default")
      (node (ref "X-NORTH") (pin "38") (pinfunction "38_38") (pintype "bidirectional"))
    )
    (net (code "124") (name "OUT38_P") (class "Default")
      (node (ref "X-NORTH") (pin "40") (pinfunction "40_40") (pintype "bidirectional"))
    )
    (net (code "125") (name "OUT39_N") (class "Default")
      (node (ref "X-NORTH") (pin "39") (pinfunction "39_39") (pintype "bidirectional"))
      (node (ref "X-WEST") (pin "80") (pinfunction "80_80") (pintype "bidirectional"))
    )
    (net (code "126") (name "OUT39_P") (class "Default")
      (node (ref "X-NORTH") (pin "41") (pinfunction "41_41") (pintype "bidirectional"))
      (node (ref "X-WEST") (pin "78") (pinfunction "78_78") (pintype "bidirectional"))
    )
    (net (code "127") (name "OUT40_N") (class "Default")
      (node (ref "X-NORTH") (pin "44") (pinfunction "44_44") (pintype "bidirectional"))
    )
    (net (code "128") (name "OUT40_P") (class "Default")
      (node (ref "X-NORTH") (pin "46") (pinfunction "46_46") (pintype "bidirectional"))
    )
    (net (code "129") (name "OUT41_N") (class "Default")
      (node (ref "X-NORTH") (pin "45") (pinfunction "45_45") (pintype "bidirectional"))
      (node (ref "X-WEST") (pin "74") (pinfunction "74_74") (pintype "bidirectional"))
    )
    (net (code "130") (name "OUT41_P") (class "Default")
      (node (ref "X-NORTH") (pin "47") (pinfunction "47_47") (pintype "bidirectional"))
      (node (ref "X-WEST") (pin "72") (pinfunction "72_72") (pintype "bidirectional"))
    )
    (net (code "131") (name "OUT42_N") (class "Default")
      (node (ref "X-NORTH") (pin "50") (pinfunction "50_50") (pintype "bidirectional"))
    )
    (net (code "132") (name "OUT42_P") (class "Default")
      (node (ref "X-NORTH") (pin "52") (pinfunction "52_52") (pintype "bidirectional"))
    )
    (net (code "133") (name "OUT43_N") (class "Default")
      (node (ref "X-NORTH") (pin "51") (pinfunction "51_51") (pintype "bidirectional"))
      (node (ref "X-WEST") (pin "68") (pinfunction "68_68") (pintype "bidirectional"))
    )
    (net (code "134") (name "OUT43_P") (class "Default")
      (node (ref "X-NORTH") (pin "53") (pinfunction "53_53") (pintype "bidirectional"))
      (node (ref "X-WEST") (pin "66") (pinfunction "66_66") (pintype "bidirectional"))
    )
    (net (code "135") (name "OUT44_N") (class "Default")
      (node (ref "X-NORTH") (pin "56") (pinfunction "56_56") (pintype "bidirectional"))
    )
    (net (code "136") (name "OUT44_P") (class "Default")
      (node (ref "X-NORTH") (pin "58") (pinfunction "58_58") (pintype "bidirectional"))
    )
    (net (code "137") (name "OUT45_N") (class "Default")
      (node (ref "X-NORTH") (pin "57") (pinfunction "57_57") (pintype "bidirectional"))
      (node (ref "X-WEST") (pin "62") (pinfunction "62_62") (pintype "bidirectional"))
    )
    (net (code "138") (name "OUT45_P") (class "Default")
      (node (ref "X-NORTH") (pin "59") (pinfunction "59_59") (pintype "bidirectional"))
      (node (ref "X-WEST") (pin "60") (pinfunction "60_60") (pintype "bidirectional"))
    )
    (net (code "139") (name "OUT46_N") (class "Default")
      (node (ref "X-NORTH") (pin "62") (pinfunction "62_62") (pintype "bidirectional"))
    )
    (net (code "140") (name "OUT46_P") (class "Default")
      (node (ref "X-NORTH") (pin "64") (pinfunction "64_64") (pintype "bidirectional"))
    )
    (net (code "141") (name "OUT47_N") (class "Default")
      (node (ref "X-NORTH") (pin "63") (pinfunction "63_63") (pintype "bidirectional"))
      (node (ref "X-WEST") (pin "56") (pinfunction "56_56") (pintype "bidirectional"))
    )
    (net (code "142") (name "OUT47_P") (class "Default")
      (node (ref "X-NORTH") (pin "65") (pinfunction "65_65") (pintype "bidirectional"))
      (node (ref "X-WEST") (pin "54") (pinfunction "54_54") (pintype "bidirectional"))
    )
    (net (code "143") (name "OUT48_N") (class "Default")
      (node (ref "X-NORTH") (pin "68") (pinfunction "68_68") (pintype "bidirectional"))
    )
    (net (code "144") (name "OUT48_P") (class "Default")
      (node (ref "X-NORTH") (pin "70") (pinfunction "70_70") (pintype "bidirectional"))
    )
    (net (code "145") (name "OUT49_N") (class "Default")
      (node (ref "X-EAST") (pin "48") (pinfunction "48_48") (pintype "bidirectional"))
      (node (ref "X-NORTH") (pin "74") (pinfunction "74_74") (pintype "bidirectional"))
    )
    (net (code "146") (name "OUT49_P") (class "Default")
      (node (ref "X-EAST") (pin "46") (pinfunction "46_46") (pintype "bidirectional"))
      (node (ref "X-NORTH") (pin "76") (pinfunction "76_76") (pintype "bidirectional"))
    )
    (net (code "147") (name "OUT50_N") (class "Default")
      (node (ref "X-NORTH") (pin "69") (pinfunction "69_69") (pintype "bidirectional"))
    )
    (net (code "148") (name "OUT50_P") (class "Default")
      (node (ref "X-NORTH") (pin "71") (pinfunction "71_71") (pintype "bidirectional"))
    )
    (net (code "149") (name "OUT51_N") (class "Default")
      (node (ref "X-EAST") (pin "42") (pinfunction "42_42") (pintype "bidirectional"))
      (node (ref "X-NORTH") (pin "80") (pinfunction "80_80") (pintype "bidirectional"))
    )
    (net (code "150") (name "OUT51_P") (class "Default")
      (node (ref "X-EAST") (pin "40") (pinfunction "40_40") (pintype "bidirectional"))
      (node (ref "X-NORTH") (pin "82") (pinfunction "82_82") (pintype "bidirectional"))
    )
    (net (code "151") (name "OUT52_N") (class "Default")
      (node (ref "X-NORTH") (pin "75") (pinfunction "75_75") (pintype "bidirectional"))
    )
    (net (code "152") (name "OUT52_P") (class "Default")
      (node (ref "X-NORTH") (pin "77") (pinfunction "77_77") (pintype "bidirectional"))
    )
    (net (code "153") (name "OUT53_N") (class "Default")
      (node (ref "X-EAST") (pin "47") (pinfunction "47_47") (pintype "bidirectional"))
      (node (ref "X-NORTH") (pin "86") (pinfunction "86_86") (pintype "bidirectional"))
    )
    (net (code "154") (name "OUT53_P") (class "Default")
      (node (ref "X-EAST") (pin "45") (pinfunction "45_45") (pintype "bidirectional"))
      (node (ref "X-NORTH") (pin "88") (pinfunction "88_88") (pintype "bidirectional"))
    )
    (net (code "155") (name "OUT54_N") (class "Default")
      (node (ref "X-NORTH") (pin "81") (pinfunction "81_81") (pintype "bidirectional"))
    )
    (net (code "156") (name "OUT54_P") (class "Default")
      (node (ref "X-NORTH") (pin "83") (pinfunction "83_83") (pintype "bidirectional"))
    )
    (net (code "157") (name "OUT55_N") (class "Default")
      (node (ref "X-EAST") (pin "41") (pinfunction "41_41") (pintype "bidirectional"))
      (node (ref "X-NORTH") (pin "92") (pinfunction "92_92") (pintype "bidirectional"))
    )
    (net (code "158") (name "OUT55_P") (class "Default")
      (node (ref "X-EAST") (pin "39") (pinfunction "39_39") (pintype "bidirectional"))
      (node (ref "X-NORTH") (pin "94") (pinfunction "94_94") (pintype "bidirectional"))
    )
    (net (code "159") (name "OUT56_N") (class "Default")
      (node (ref "X-NORTH") (pin "87") (pinfunction "87_87") (pintype "bidirectional"))
    )
    (net (code "160") (name "OUT56_P") (class "Default")
      (node (ref "X-NORTH") (pin "89") (pinfunction "89_89") (pintype "bidirectional"))
    )
    (net (code "161") (name "OUT57_N") (class "Default")
      (node (ref "X-EAST") (pin "35") (pinfunction "35_35") (pintype "bidirectional"))
      (node (ref "X-NORTH") (pin "98") (pinfunction "98_98") (pintype "bidirectional"))
    )
    (net (code "162") (name "OUT57_P") (class "Default")
      (node (ref "X-EAST") (pin "33") (pinfunction "33_33") (pintype "bidirectional"))
      (node (ref "X-NORTH") (pin "100") (pinfunction "100_100") (pintype "bidirectional"))
    )
    (net (code "163") (name "OUT58_N") (class "Default")
      (node (ref "X-NORTH") (pin "93") (pinfunction "93_93") (pintype "bidirectional"))
    )
    (net (code "164") (name "OUT58_P") (class "Default")
      (node (ref "X-NORTH") (pin "95") (pinfunction "95_95") (pintype "bidirectional"))
    )
    (net (code "165") (name "OUT59_N") (class "Default")
      (node (ref "X-EAST") (pin "27") (pinfunction "27_27") (pintype "bidirectional"))
      (node (ref "X-NORTH") (pin "104") (pinfunction "104_104") (pintype "bidirectional"))
    )
    (net (code "166") (name "OUT59_P") (class "Default")
      (node (ref "X-EAST") (pin "25") (pinfunction "25_25") (pintype "bidirectional"))
      (node (ref "X-NORTH") (pin "106") (pinfunction "106_106") (pintype "bidirectional"))
    )
    (net (code "167") (name "OUT60_N") (class "Default")
      (node (ref "X-NORTH") (pin "110") (pinfunction "110_110") (pintype "bidirectional"))
    )
    (net (code "168") (name "OUT60_P") (class "Default")
      (node (ref "X-NORTH") (pin "112") (pinfunction "112_112") (pintype "bidirectional"))
    )
    (net (code "169") (name "OUT61_N") (class "Default")
      (node (ref "X-EAST") (pin "36") (pinfunction "36_36") (pintype "bidirectional"))
      (node (ref "X-NORTH") (pin "99") (pinfunction "99_99") (pintype "bidirectional"))
    )
    (net (code "170") (name "OUT61_P") (class "Default")
      (node (ref "X-EAST") (pin "34") (pinfunction "34_34") (pintype "bidirectional"))
      (node (ref "X-NORTH") (pin "101") (pinfunction "101_101") (pintype "bidirectional"))
    )
    (net (code "171") (name "OUT62_N") (class "Default")
      (node (ref "X-NORTH") (pin "116") (pinfunction "116_116") (pintype "bidirectional"))
    )
    (net (code "172") (name "OUT62_P") (class "Default")
      (node (ref "X-NORTH") (pin "118") (pinfunction "118_118") (pintype "bidirectional"))
    )
    (net (code "173") (name "OUT63_N") (class "Default")
      (node (ref "X-EAST") (pin "30") (pinfunction "30_30") (pintype "bidirectional"))
      (node (ref "X-NORTH") (pin "105") (pinfunction "105_105") (pintype "bidirectional"))
    )
    (net (code "174") (name "OUT63_P") (class "Default")
      (node (ref "X-EAST") (pin "28") (pinfunction "28_28") (pintype "bidirectional"))
      (node (ref "X-NORTH") (pin "107") (pinfunction "107_107") (pintype "bidirectional"))
    )
    (net (code "175") (name "OUT64_N") (class "Default")
      (node (ref "X-NORTH") (pin "111") (pinfunction "111_111") (pintype "bidirectional"))
    )
    (net (code "176") (name "OUT64_P") (class "Default")
      (node (ref "X-NORTH") (pin "113") (pinfunction "113_113") (pintype "bidirectional"))
    )
    (net (code "177") (name "OUTCLK_N") (class "Default")
      (node (ref "X-NORTH") (pin "15") (pinfunction "15_15") (pintype "bidirectional"))
      (node (ref "X-WEST") (pin "53") (pinfunction "53_53") (pintype "bidirectional"))
    )
    (net (code "178") (name "OUTCLK_P") (class "Default")
      (node (ref "X-NORTH") (pin "17") (pinfunction "17_17") (pintype "bidirectional"))
      (node (ref "X-WEST") (pin "55") (pinfunction "55_55") (pintype "bidirectional"))
    )
    (net (code "179") (name "OUTCTR_N") (class "Default")
      (node (ref "X-SOUTH") (pin "125") (pinfunction "125_125") (pintype "bidirectional"))
      (node (ref "X-WEST") (pin "22") (pinfunction "22_22") (pintype "bidirectional"))
    )
    (net (code "180") (name "OUTCTR_P") (class "Default")
      (node (ref "X-SOUTH") (pin "123") (pinfunction "123_123") (pintype "bidirectional"))
      (node (ref "X-WEST") (pin "24") (pinfunction "24_24") (pintype "bidirectional"))
    )
    (net (code "181") (name "RES1") (class "Default")
      (node (ref "X-WEST") (pin "79") (pinfunction "79_79") (pintype "bidirectional"))
    )
    (net (code "182") (name "RES2") (class "Default")
      (node (ref "X-WEST") (pin "81") (pinfunction "81_81") (pintype "bidirectional"))
    )
    (net (code "183") (name "RES3") (class "Default")
      (node (ref "X-WEST") (pin "83") (pinfunction "83_83") (pintype "bidirectional"))
    )
    (net (code "184") (name "RES4") (class "Default")
      (node (ref "X-EAST") (pin "79") (pinfunction "79_79") (pintype "bidirectional"))
    )
    (net (code "185") (name "RES5") (class "Default")
      (node (ref "X-EAST") (pin "81") (pinfunction "81_81") (pintype "bidirectional"))
    )
    (net (code "186") (name "RES6") (class "Default")
      (node (ref "X-EAST") (pin "83") (pinfunction "83_83") (pintype "bidirectional"))
    )
    (net (code "187") (name "S00_N") (class "Default")
      (node (ref "X-SOUTH") (pin "16") (pinfunction "16_16") (pintype "bidirectional"))
    )
    (net (code "188") (name "S00_P") (class "Default")
      (node (ref "X-SOUTH") (pin "14") (pinfunction "14_14") (pintype "bidirectional"))
    )
    (net (code "189") (name "S01_N") (class "Default")
      (node (ref "X-SOUTH") (pin "17") (pinfunction "17_17") (pintype "bidirectional"))
    )
    (net (code "190") (name "S01_P") (class "Default")
      (node (ref "X-SOUTH") (pin "15") (pinfunction "15_15") (pintype "bidirectional"))
    )
    (net (code "191") (name "S02_N") (class "Default")
      (node (ref "X-SOUTH") (pin "22") (pinfunction "22_22") (pintype "bidirectional"))
    )
    (net (code "192") (name "S02_P") (class "Default")
      (node (ref "X-SOUTH") (pin "20") (pinfunction "20_20") (pintype "bidirectional"))
    )
    (net (code "193") (name "S03_N") (class "Default")
      (node (ref "X-SOUTH") (pin "23") (pinfunction "23_23") (pintype "bidirectional"))
    )
    (net (code "194") (name "S03_P") (class "Default")
      (node (ref "X-SOUTH") (pin "21") (pinfunction "21_21") (pintype "bidirectional"))
    )
    (net (code "195") (name "S05_N") (class "Default")
      (node (ref "X-SOUTH") (pin "29") (pinfunction "29_29") (pintype "bidirectional"))
    )
    (net (code "196") (name "S05_P") (class "Default")
      (node (ref "X-SOUTH") (pin "27") (pinfunction "27_27") (pintype "bidirectional"))
    )
    (net (code "197") (name "S38_N") (class "Default")
      (node (ref "X-SOUTH") (pin "130") (pinfunction "130_130") (pintype "bidirectional"))
    )
    (net (code "198") (name "S38_P") (class "Default")
      (node (ref "X-SOUTH") (pin "128") (pinfunction "128_128") (pintype "bidirectional"))
    )
    (net (code "199") (name "S39_N") (class "Default")
      (node (ref "X-SOUTH") (pin "131") (pinfunction "131_131") (pintype "bidirectional"))
    )
    (net (code "200") (name "S39_P") (class "Default")
      (node (ref "X-SOUTH") (pin "129") (pinfunction "129_129") (pintype "bidirectional"))
    )
    (net (code "201") (name "SYS_RES_N") (class "Default")
      (node (ref "X-EAST") (pin "22") (pinfunction "22_22") (pintype "bidirectional"))
      (node (ref "X-NORTH") (pin "125") (pinfunction "125_125") (pintype "bidirectional"))
    )
    (net (code "202") (name "S_CHK_EN") (class "Default")
      (node (ref "X-EAST") (pin "94") (pinfunction "94_94") (pintype "bidirectional"))
      (node (ref "X-SOUTH") (pin "8") (pinfunction "8_8") (pintype "bidirectional"))
    )
    (net (code "203") (name "S_CHK_V") (class "Default")
      (node (ref "X-EAST") (pin "92") (pinfunction "92_92") (pintype "bidirectional"))
      (node (ref "X-SOUTH") (pin "10") (pinfunction "10_10") (pintype "bidirectional"))
    )
    (net (code "204") (name "S_I2C_EN") (class "Default")
      (node (ref "X-SOUTH") (pin "137") (pinfunction "137_137") (pintype "bidirectional"))
      (node (ref "X-WEST") (pin "7") (pinfunction "7_7") (pintype "bidirectional"))
    )
    (net (code "205") (name "S_I2C_V") (class "Default")
      (node (ref "X-SOUTH") (pin "135") (pinfunction "135_135") (pintype "bidirectional"))
      (node (ref "X-WEST") (pin "9") (pinfunction "9_9") (pintype "bidirectional"))
    )
    (net (code "206") (name "S_SCK") (class "Default")
      (node (ref "X-SOUTH") (pin "144") (pinfunction "144_144") (pintype "bidirectional"))
      (node (ref "X-WEST") (pin "2") (pinfunction "2_2") (pintype "bidirectional"))
    )
    (net (code "207") (name "S_SCL") (class "Default")
      (node (ref "X-SOUTH") (pin "143") (pinfunction "143_143") (pintype "bidirectional"))
      (node (ref "X-WEST") (pin "1") (pinfunction "1_1") (pintype "bidirectional"))
    )
    (net (code "208") (name "S_SDA") (class "Default")
      (node (ref "X-SOUTH") (pin "141") (pinfunction "141_141") (pintype "bidirectional"))
      (node (ref "X-WEST") (pin "3") (pinfunction "3_3") (pintype "bidirectional"))
    )
    (net (code "209") (name "S_SDI") (class "Default")
      (node (ref "X-SOUTH") (pin "140") (pinfunction "140_140") (pintype "bidirectional"))
      (node (ref "X-WEST") (pin "6") (pinfunction "6_6") (pintype "bidirectional"))
    )
    (net (code "210") (name "S_SDO") (class "Default")
      (node (ref "X-SOUTH") (pin "142") (pinfunction "142_142") (pintype "bidirectional"))
      (node (ref "X-WEST") (pin "4") (pinfunction "4_4") (pintype "bidirectional"))
    )
    (net (code "211") (name "S_SPI_EN") (class "Default")
      (node (ref "X-SOUTH") (pin "136") (pinfunction "136_136") (pintype "bidirectional"))
      (node (ref "X-WEST") (pin "8") (pinfunction "8_8") (pintype "bidirectional"))
    )
    (net (code "212") (name "S_SPI_V") (class "Default")
      (node (ref "X-SOUTH") (pin "134") (pinfunction "134_134") (pintype "bidirectional"))
      (node (ref "X-WEST") (pin "10") (pinfunction "10_10") (pintype "bidirectional"))
    )
    (net (code "213") (name "S_VE") (class "Default")
      (node (ref "C7") (pin "1") (pinfunction "1_1") (pintype "passive"))
      (node (ref "SE") (pin "1") (pinfunction "1_1") (pintype "passive"))
      (node (ref "X-SOUTH") (pin "13") (pinfunction "13_13") (pintype "bidirectional"))
      (node (ref "X-SOUTH") (pin "19") (pinfunction "19_19") (pintype "bidirectional"))
      (node (ref "X-SOUTH") (pin "31") (pinfunction "31_31") (pintype "bidirectional"))
      (node (ref "X-SOUTH") (pin "37") (pinfunction "37_37") (pintype "bidirectional"))
    )
    (net (code "214") (name "S_VE_CV") (class "Default")
      (node (ref "X-EAST") (pin "100") (pinfunction "100_100") (pintype "bidirectional"))
      (node (ref "X-SOUTH") (pin "2") (pinfunction "2_2") (pintype "bidirectional"))
    )
    (net (code "215") (name "S_VE_OV") (class "Default")
      (node (ref "X-EAST") (pin "99") (pinfunction "99_99") (pintype "bidirectional"))
      (node (ref "X-SOUTH") (pin "1") (pinfunction "1_1") (pintype "bidirectional"))
    )
    (net (code "216") (name "S_VE_RS") (class "Default")
      (node (ref "X-EAST") (pin "84") (pinfunction "84_84") (pintype "bidirectional"))
      (node (ref "X-SOUTH") (pin "25") (pinfunction "25_25") (pintype "bidirectional"))
    )
    (net (code "217") (name "S_VE_UV") (class "Default")
      (node (ref "X-EAST") (pin "89") (pinfunction "89_89") (pintype "bidirectional"))
      (node (ref "X-SOUTH") (pin "7") (pinfunction "7_7") (pintype "bidirectional"))
    )
    (net (code "218") (name "S_VS") (class "Default")
      (node (ref "C6") (pin "1") (pinfunction "1_1") (pintype "passive"))
      (node (ref "SW") (pin "1") (pinfunction "1_1") (pintype "passive"))
      (node (ref "X-SOUTH") (pin "49") (pinfunction "49_49") (pintype "bidirectional"))
      (node (ref "X-SOUTH") (pin "55") (pinfunction "55_55") (pintype "bidirectional"))
      (node (ref "X-SOUTH") (pin "61") (pinfunction "61_61") (pintype "bidirectional"))
      (node (ref "X-SOUTH") (pin "67") (pinfunction "67_67") (pintype "bidirectional"))
      (node (ref "X-SOUTH") (pin "79") (pinfunction "79_79") (pintype "bidirectional"))
      (node (ref "X-SOUTH") (pin "85") (pinfunction "85_85") (pintype "bidirectional"))
      (node (ref "X-SOUTH") (pin "91") (pinfunction "91_91") (pintype "bidirectional"))
      (node (ref "X-SOUTH") (pin "97") (pinfunction "97_97") (pintype "bidirectional"))
    )
    (net (code "219") (name "S_VS_CV") (class "Default")
      (node (ref "X-EAST") (pin "98") (pinfunction "98_98") (pintype "bidirectional"))
      (node (ref "X-SOUTH") (pin "4") (pinfunction "4_4") (pintype "bidirectional"))
    )
    (net (code "220") (name "S_VS_OV") (class "Default")
      (node (ref "X-EAST") (pin "97") (pinfunction "97_97") (pintype "bidirectional"))
      (node (ref "X-SOUTH") (pin "3") (pinfunction "3_3") (pintype "bidirectional"))
    )
    (net (code "221") (name "S_VS_RS") (class "Default")
      (node (ref "X-EAST") (pin "86") (pinfunction "86_86") (pintype "bidirectional"))
      (node (ref "X-SOUTH") (pin "73") (pinfunction "73_73") (pintype "bidirectional"))
    )
    (net (code "222") (name "S_VS_UV") (class "Default")
      (node (ref "X-EAST") (pin "87") (pinfunction "87_87") (pintype "bidirectional"))
      (node (ref "X-SOUTH") (pin "9") (pinfunction "9_9") (pintype "bidirectional"))
    )
    (net (code "223") (name "S_VW") (class "Default")
      (node (ref "C2") (pin "1") (pinfunction "1_1") (pintype "passive"))
      (node (ref "SW") (pin "2") (pinfunction "2_2") (pintype "passive"))
      (node (ref "X-SOUTH") (pin "109") (pinfunction "109_109") (pintype "bidirectional"))
      (node (ref "X-SOUTH") (pin "115") (pinfunction "115_115") (pintype "bidirectional"))
      (node (ref "X-SOUTH") (pin "127") (pinfunction "127_127") (pintype "bidirectional"))
      (node (ref "X-SOUTH") (pin "133") (pinfunction "133_133") (pintype "bidirectional"))
    )
    (net (code "224") (name "S_VW_CV") (class "Default")
      (node (ref "X-EAST") (pin "96") (pinfunction "96_96") (pintype "bidirectional"))
      (node (ref "X-SOUTH") (pin "6") (pinfunction "6_6") (pintype "bidirectional"))
    )
    (net (code "225") (name "S_VW_OV") (class "Default")
      (node (ref "X-EAST") (pin "95") (pinfunction "95_95") (pintype "bidirectional"))
      (node (ref "X-SOUTH") (pin "5") (pinfunction "5_5") (pintype "bidirectional"))
    )
    (net (code "226") (name "S_VW_RS") (class "Default")
      (node (ref "X-EAST") (pin "88") (pinfunction "88_88") (pintype "bidirectional"))
      (node (ref "X-SOUTH") (pin "121") (pinfunction "121_121") (pintype "bidirectional"))
    )
    (net (code "227") (name "S_VW_UV") (class "Default")
      (node (ref "X-EAST") (pin "85") (pinfunction "85_85") (pintype "bidirectional"))
      (node (ref "X-SOUTH") (pin "11") (pinfunction "11_11") (pintype "bidirectional"))
    )
    (net (code "228") (name "TCK") (class "Default")
      (node (ref "X-WEST") (pin "12") (pinfunction "12_12") (pintype "bidirectional"))
    )
    (net (code "229") (name "TDI") (class "Default")
      (node (ref "X-WEST") (pin "16") (pinfunction "16_16") (pintype "bidirectional"))
    )
    (net (code "230") (name "TDIG1") (class "Default")
      (node (ref "X-EAST") (pin "18") (pinfunction "18_18") (pintype "bidirectional"))
      (node (ref "X-NORTH") (pin "123") (pinfunction "123_123") (pintype "bidirectional"))
    )
    (net (code "231") (name "TDIG2") (class "Default")
      (node (ref "X-NORTH") (pin "130") (pinfunction "130_130") (pintype "bidirectional"))
    )
    (net (code "232") (name "TDO") (class "Default")
      (node (ref "X-WEST") (pin "18") (pinfunction "18_18") (pintype "bidirectional"))
    )
    (net (code "233") (name "TMS") (class "Default")
      (node (ref "X-WEST") (pin "14") (pinfunction "14_14") (pintype "bidirectional"))
    )
    (net (code "234") (name "T_EXP1") (class "Default")
      (node (ref "X-EAST") (pin "12") (pinfunction "12_12") (pintype "bidirectional"))
      (node (ref "X-NORTH") (pin "131") (pinfunction "131_131") (pintype "bidirectional"))
    )
    (net (code "235") (name "T_EXP2") (class "Default")
      (node (ref "X-EAST") (pin "16") (pinfunction "16_16") (pintype "bidirectional"))
      (node (ref "X-NORTH") (pin "119") (pinfunction "119_119") (pintype "bidirectional"))
    )
    (net (code "236") (name "W_EN") (class "Default")
      (node (ref "X-WEST") (pin "19") (pinfunction "19_19") (pintype "bidirectional"))
    )
    (net (code "237") (name "W_I2C_EN") (class "Default")
      (node (ref "X-WEST") (pin "13") (pinfunction "13_13") (pintype "bidirectional"))
    )
    (net (code "238") (name "W_I2C_V") (class "Default")
      (node (ref "X-WEST") (pin "11") (pinfunction "11_11") (pintype "bidirectional"))
    )
    (net (code "239") (name "W_SCL") (class "Default")
      (node (ref "X-WEST") (pin "15") (pinfunction "15_15") (pintype "bidirectional"))
    )
    (net (code "240") (name "W_SDA") (class "Default")
      (node (ref "X-WEST") (pin "17") (pinfunction "17_17") (pintype "bidirectional"))
    )
    (net (code "241") (name "W_VW") (class "Default")
      (node (ref "C8") (pin "1") (pinfunction "1_1") (pintype "passive"))
      (node (ref "NW") (pin "2") (pinfunction "2_2") (pintype "passive"))
    )
    (net (code "242") (name "W_VW_CV") (class "Default")
      (node (ref "X-WEST") (pin "90") (pinfunction "90_90") (pintype "bidirectional"))
    )
    (net (code "243") (name "W_VW_OV") (class "Default")
      (node (ref "X-WEST") (pin "93") (pinfunction "93_93") (pintype "bidirectional"))
    )
    (net (code "244") (name "W_VW_UV") (class "Default")
      (node (ref "X-WEST") (pin "91") (pinfunction "91_91") (pintype "bidirectional"))
    )
    (net (code "245") (name "unconnected-(X-EAST-PadM1)") (class "Default")
      (node (ref "X-EAST") (pin "M1") (pinfunction "M1_M1") (pintype "bidirectional"))
    )
    (net (code "246") (name "unconnected-(X-EAST-PadM2)") (class "Default")
      (node (ref "X-EAST") (pin "M2") (pinfunction "M2_M2") (pintype "bidirectional"))
    )
    (net (code "247") (name "unconnected-(X-NORTH-PadM1)") (class "Default")
      (node (ref "X-NORTH") (pin "M1") (pinfunction "M1_M1") (pintype "bidirectional"))
    )
    (net (code "248") (name "unconnected-(X-NORTH-PadM2)") (class "Default")
      (node (ref "X-NORTH") (pin "M2") (pinfunction "M2_M2") (pintype "bidirectional"))
    )
    (net (code "249") (name "unconnected-(X-SOUTH-PadM1)") (class "Default")
      (node (ref "X-SOUTH") (pin "M1") (pinfunction "M1_M1") (pintype "bidirectional"))
    )
    (net (code "250") (name "unconnected-(X-SOUTH-PadM2)") (class "Default")
      (node (ref "X-SOUTH") (pin "M2") (pinfunction "M2_M2") (pintype "bidirectional"))
    )
    (net (code "251") (name "unconnected-(X-WEST-PadM1)") (class "Default")
      (node (ref "X-WEST") (pin "M1") (pinfunction "M1_M1") (pintype "bidirectional"))
    )
    (net (code "252") (name "unconnected-(X-WEST-PadM2)") (class "Default")
      (node (ref "X-WEST") (pin "M2") (pinfunction "M2_M2") (pintype "bidirectional"))
    )
  )
)
